# HIGH_CURR_MOS2.net
KiCad netlist of a schematic drawn in Altium Designer
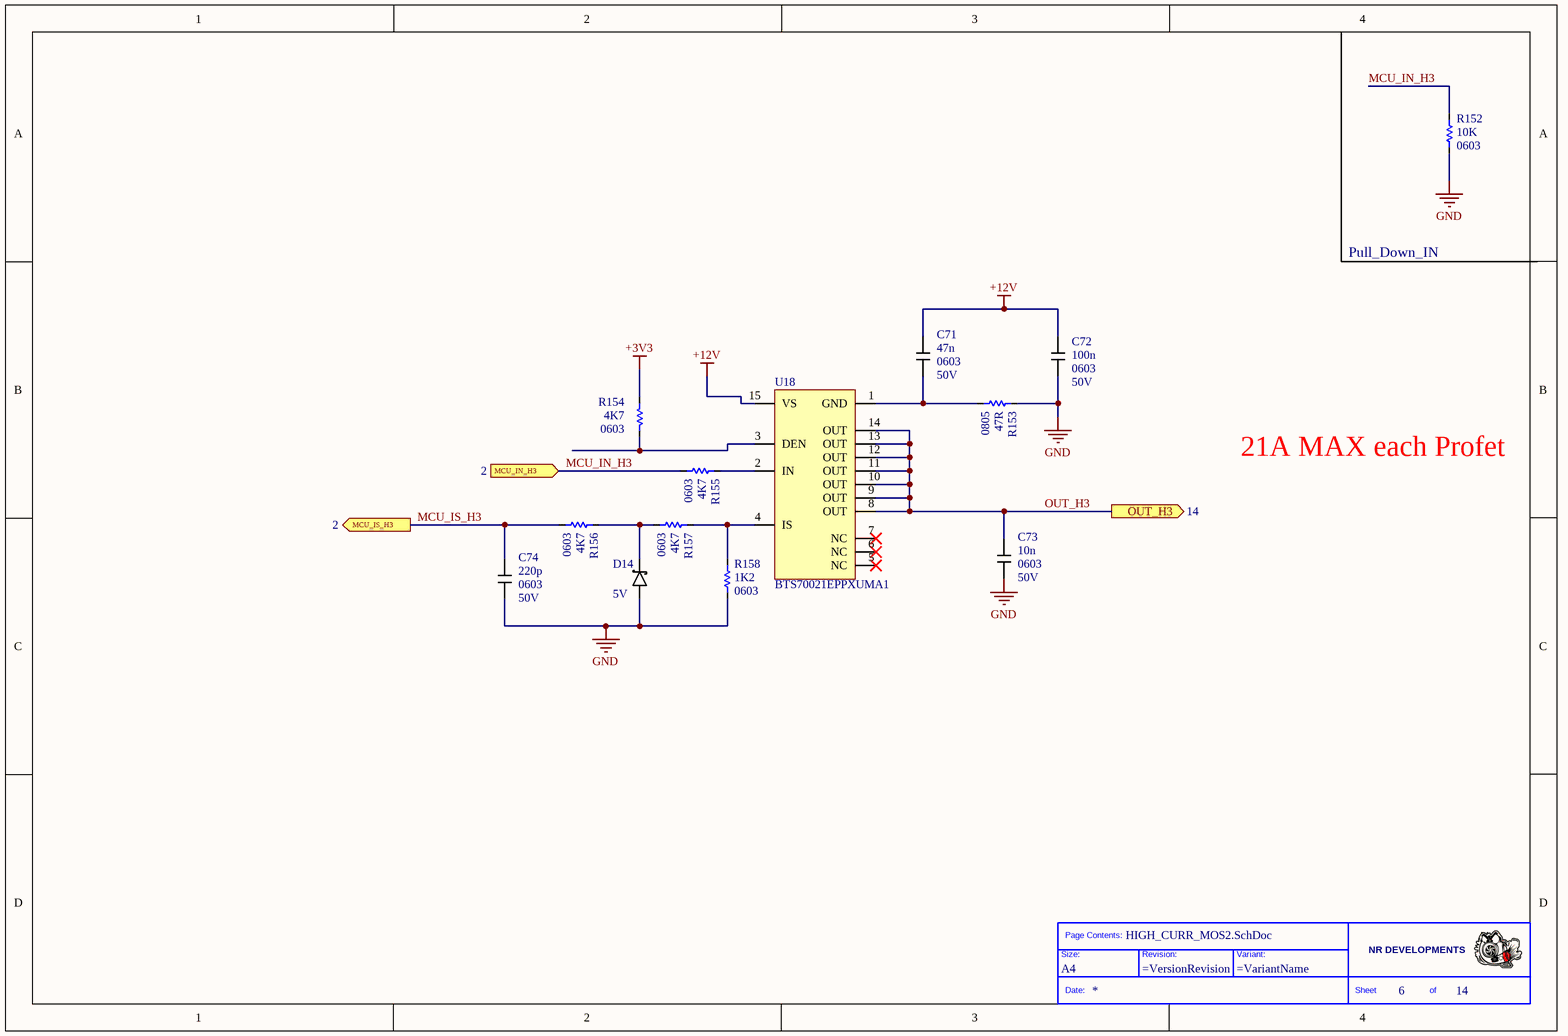
[diagram p0: HIGH_CURR_MOS2.SchDoc]

(export (version "E")
  (design (tool "Eeschema 10.0.6"))
  (components
    (comp (ref "C71")
      (value "47n")
      (footprint "CAPC1608X09M")
      (fields
        (field (name "MANUFACTURER") "KEMET")
        (field (name "PARTNUMBER") "C0603C473M5RACTU")
        (field (name "CASE") "0603")
        (field (name "VOLTAGE") "50V")
        (field (name "Comment") "CAP")
      )
      (libsource (lib "My_LIB") (part "CAP"))
    )
    (comp (ref "C72")
      (value "100n")
      (footprint "CAPC1608X09M")
      (fields
        (field (name "CASE") "0603")
        (field (name "VOLTAGE") "50V")
        (field (name "MANUFACTURER") "KEMET")
        (field (name "PARTNUMBER") "C0603C104K5RACTU")
        (field (name "Comment") "CAP")
      )
      (libsource (lib "My_LIB") (part "CAP"))
    )
    (comp (ref "C73")
      (value "10n")
      (footprint "CAPC1608X09M")
      (fields
        (field (name "MANUFACTURER") "KEMET")
        (field (name "PARTNUMBER") "C0603C103M5RACTM")
        (field (name "CASE") "0603")
        (field (name "VOLTAGE") "50V")
        (field (name "Comment") "CAP")
      )
      (libsource (lib "My_LIB") (part "CAP"))
    )
    (comp (ref "C74")
      (value "220p")
      (footprint "CAPC1608X09M")
      (fields
        (field (name "MANUFACTURER") "KEMET")
        (field (name "PARTNUMBER") "C0603C221J5RACTU")
        (field (name "CASE") "0603")
        (field (name "VOLTAGE") "50V")
        (field (name "Comment") "CAP")
      )
      (libsource (lib "My_LIB") (part "CAP"))
    )
    (comp (ref "D14")
      (value "5V")
      (footprint "SOT65P210X100-3N - AC")
      (fields
        (field (name "MANUFACTURER") "Nexperia")
        (field (name "PARTNUMBER") "BZX84W-C4V7-QX")
        (field (name "Comment") "Diode_Schottky")
      )
      (libsource (lib "My_LIB") (part "Diode_Schottky"))
    )
    (comp (ref "R152")
      (value "10K")
      (footprint "RESC1608X06M")
      (fields
        (field (name "CASE") "0603")
        (field (name "MANUFACTURER") "YAGEO")
        (field (name "PARTNUMBER") "AC0603FR-0710KL")
        (field (name "Comment") "Res")
      )
      (libsource (lib "My_LIB") (part "Resistor"))
    )
    (comp (ref "R153")
      (value "47R")
      (footprint "RESC2012X06N")
      (fields
        (field (name "MANUFACTURER") "Vishay")
        (field (name "CASE") "0805")
        (field (name "PARTNUMBER") "CRCW080547R0FKEA")
        (field (name "Comment") "Res")
      )
      (libsource (lib "My_LIB") (part "Resistor"))
    )
    (comp (ref "R154")
      (value "4K7")
      (footprint "RESC1608X06M")
      (fields
        (field (name "CASE") "0603")
        (field (name "MANUFACTURER") "YAGEO")
        (field (name "PARTNUMBER") " RC0603FR-074K7L")
        (field (name "Comment") "Res")
      )
      (libsource (lib "My_LIB") (part "Resistor"))
    )
    (comp (ref "R155")
      (value "4K7")
      (footprint "RESC1608X06M")
      (fields
        (field (name "MANUFACTURER") "YAGEO")
        (field (name "CASE") "0603")
        (field (name "PARTNUMBER") " RC0603FR-074K7L")
        (field (name "Comment") "Res")
      )
      (libsource (lib "My_LIB") (part "Resistor"))
    )
    (comp (ref "R156")
      (value "4K7")
      (footprint "RESC1608X06M")
      (fields
        (field (name "MANUFACTURER") "YAGEO")
        (field (name "CASE") "0603")
        (field (name "PARTNUMBER") " RC0603FR-074K7L")
        (field (name "Comment") "Res")
      )
      (libsource (lib "My_LIB") (part "Resistor"))
    )
    (comp (ref "R157")
      (value "4K7")
      (footprint "RESC1608X06M")
      (fields
        (field (name "MANUFACTURER") "YAGEO")
        (field (name "CASE") "0603")
        (field (name "PARTNUMBER") " RC0603FR-074K7L")
        (field (name "Comment") "Res")
      )
      (libsource (lib "My_LIB") (part "Resistor"))
    )
    (comp (ref "R158")
      (value "1K2")
      (footprint "RESC1608X06M")
      (fields
        (field (name "MANUFACTURER") "Vishay")
        (field (name "CASE") "0603")
        (field (name "PARTNUMBER") "CRCW06031K20FKEA")
        (field (name "Comment") "Res")
      )
      (libsource (lib "My_LIB") (part "Resistor"))
    )
    (comp (ref "U18")
      (value "BTS70021EPPXUMA1")
      (footprint "SOP65P600X115-15")
      (description "Smart High-Side Power Switch 21A")
      (fields (field (name "MANUFACTURER") "Infineon Technologies") (field (name "Comment") "BTS7002-1EPP"))
      (libsource (lib "My_LIB") (part "BTS7002-1EPP"))
    )
  )
  (nets
    (net (code "1") (name "+3V3") (class "Default")
      (node (ref "R154") (pin "2") (pinfunction "2_2") (pintype "passive"))
    )
    (net (code "2") (name "+12V") (class "Default")
      (node (ref "C71") (pin "1") (pinfunction "1_1") (pintype "passive"))
      (node (ref "C72") (pin "1") (pinfunction "1_1") (pintype "passive"))
      (node (ref "U18") (pin "15") (pinfunction "VS_15") (pintype "power_in"))
    )
    (net (code "3") (name "/MCU_IN_H3") (class "Default")
      (node (ref "R152") (pin "2") (pinfunction "2_2") (pintype "passive"))
      (node (ref "R155") (pin "1") (pinfunction "1_1") (pintype "passive"))
    )
    (net (code "4") (name "/MCU_IS_H3") (class "Default")
      (node (ref "C74") (pin "1") (pinfunction "1_1") (pintype "passive"))
      (node (ref "R156") (pin "1") (pinfunction "1_1") (pintype "passive"))
    )
    (net (code "5") (name "/OUT_H3") (class "Default")
      (node (ref "C73") (pin "1") (pinfunction "1_1") (pintype "passive"))
      (node (ref "U18") (pin "10") (pinfunction "OUT_10") (pintype "passive"))
      (node (ref "U18") (pin "11") (pinfunction "OUT_11") (pintype "passive"))
      (node (ref "U18") (pin "12") (pinfunction "OUT_12") (pintype "passive"))
      (node (ref "U18") (pin "13") (pinfunction "OUT_13") (pintype "passive"))
      (node (ref "U18") (pin "14") (pinfunction "OUT_14") (pintype "passive"))
      (node (ref "U18") (pin "8") (pinfunction "OUT_8") (pintype "passive"))
      (node (ref "U18") (pin "9") (pinfunction "OUT_9") (pintype "passive"))
    )
    (net (code "6") (name "GND") (class "Default")
      (node (ref "C72") (pin "2") (pinfunction "2_2") (pintype "passive"))
      (node (ref "C73") (pin "2") (pinfunction "2_2") (pintype "passive"))
      (node (ref "C74") (pin "2") (pinfunction "2_2") (pintype "passive"))
      (node (ref "D14") (pin "A") (pinfunction "A_A") (pintype "passive"))
      (node (ref "R152") (pin "1") (pinfunction "1_1") (pintype "passive"))
      (node (ref "R153") (pin "2") (pinfunction "2_2") (pintype "passive"))
      (node (ref "R158") (pin "1") (pinfunction "1_1") (pintype "passive"))
    )
    (net (code "7") (name "Net-(D14-PadC)") (class "Default")
      (node (ref "D14") (pin "C") (pinfunction "C_C") (pintype "passive"))
      (node (ref "R156") (pin "2") (pinfunction "2_2") (pintype "passive"))
      (node (ref "R157") (pin "1") (pinfunction "1_1") (pintype "passive"))
    )
    (net (code "8") (name "Net-(U18-DEN)") (class "Default")
      (node (ref "R154") (pin "1") (pinfunction "1_1") (pintype "passive"))
      (node (ref "U18") (pin "3") (pinfunction "DEN_3") (pintype "passive"))
    )
    (net (code "9") (name "Net-(U18-GND)") (class "Default")
      (node (ref "C71") (pin "2") (pinfunction "2_2") (pintype "passive"))
      (node (ref "R153") (pin "1") (pinfunction "1_1") (pintype "passive"))
      (node (ref "U18") (pin "1") (pinfunction "GND_1") (pintype "power_in"))
    )
    (net (code "10") (name "Net-(U18-IN)") (class "Default")
      (node (ref "R155") (pin "2") (pinfunction "2_2") (pintype "passive"))
      (node (ref "U18") (pin "2") (pinfunction "IN_2") (pintype "passive"))
    )
    (net (code "11") (name "Net-(U18-IS)") (class "Default")
      (node (ref "R157") (pin "2") (pinfunction "2_2") (pintype "passive"))
      (node (ref "R158") (pin "2") (pinfunction "2_2") (pintype "passive"))
      (node (ref "U18") (pin "4") (pinfunction "IS_4") (pintype "passive"))
    )
    (net (code "12") (name "unconnected-(U18-NC-Pad5)") (class "Default")
      (node (ref "U18") (pin "5") (pinfunction "NC_5") (pintype "passive+no_connect"))
    )
    (net (code "13") (name "unconnected-(U18-NC-Pad6)") (class "Default")
      (node (ref "U18") (pin "6") (pinfunction "NC_6") (pintype "passive+no_connect"))
    )
    (net (code "14") (name "unconnected-(U18-NC-Pad7)") (class "Default")
      (node (ref "U18") (pin "7") (pinfunction "NC_7") (pintype "passive+no_connect"))
    )
  )
)
